# BrainFuino.net
KiCad netlist of a schematic drawn in EAGLE
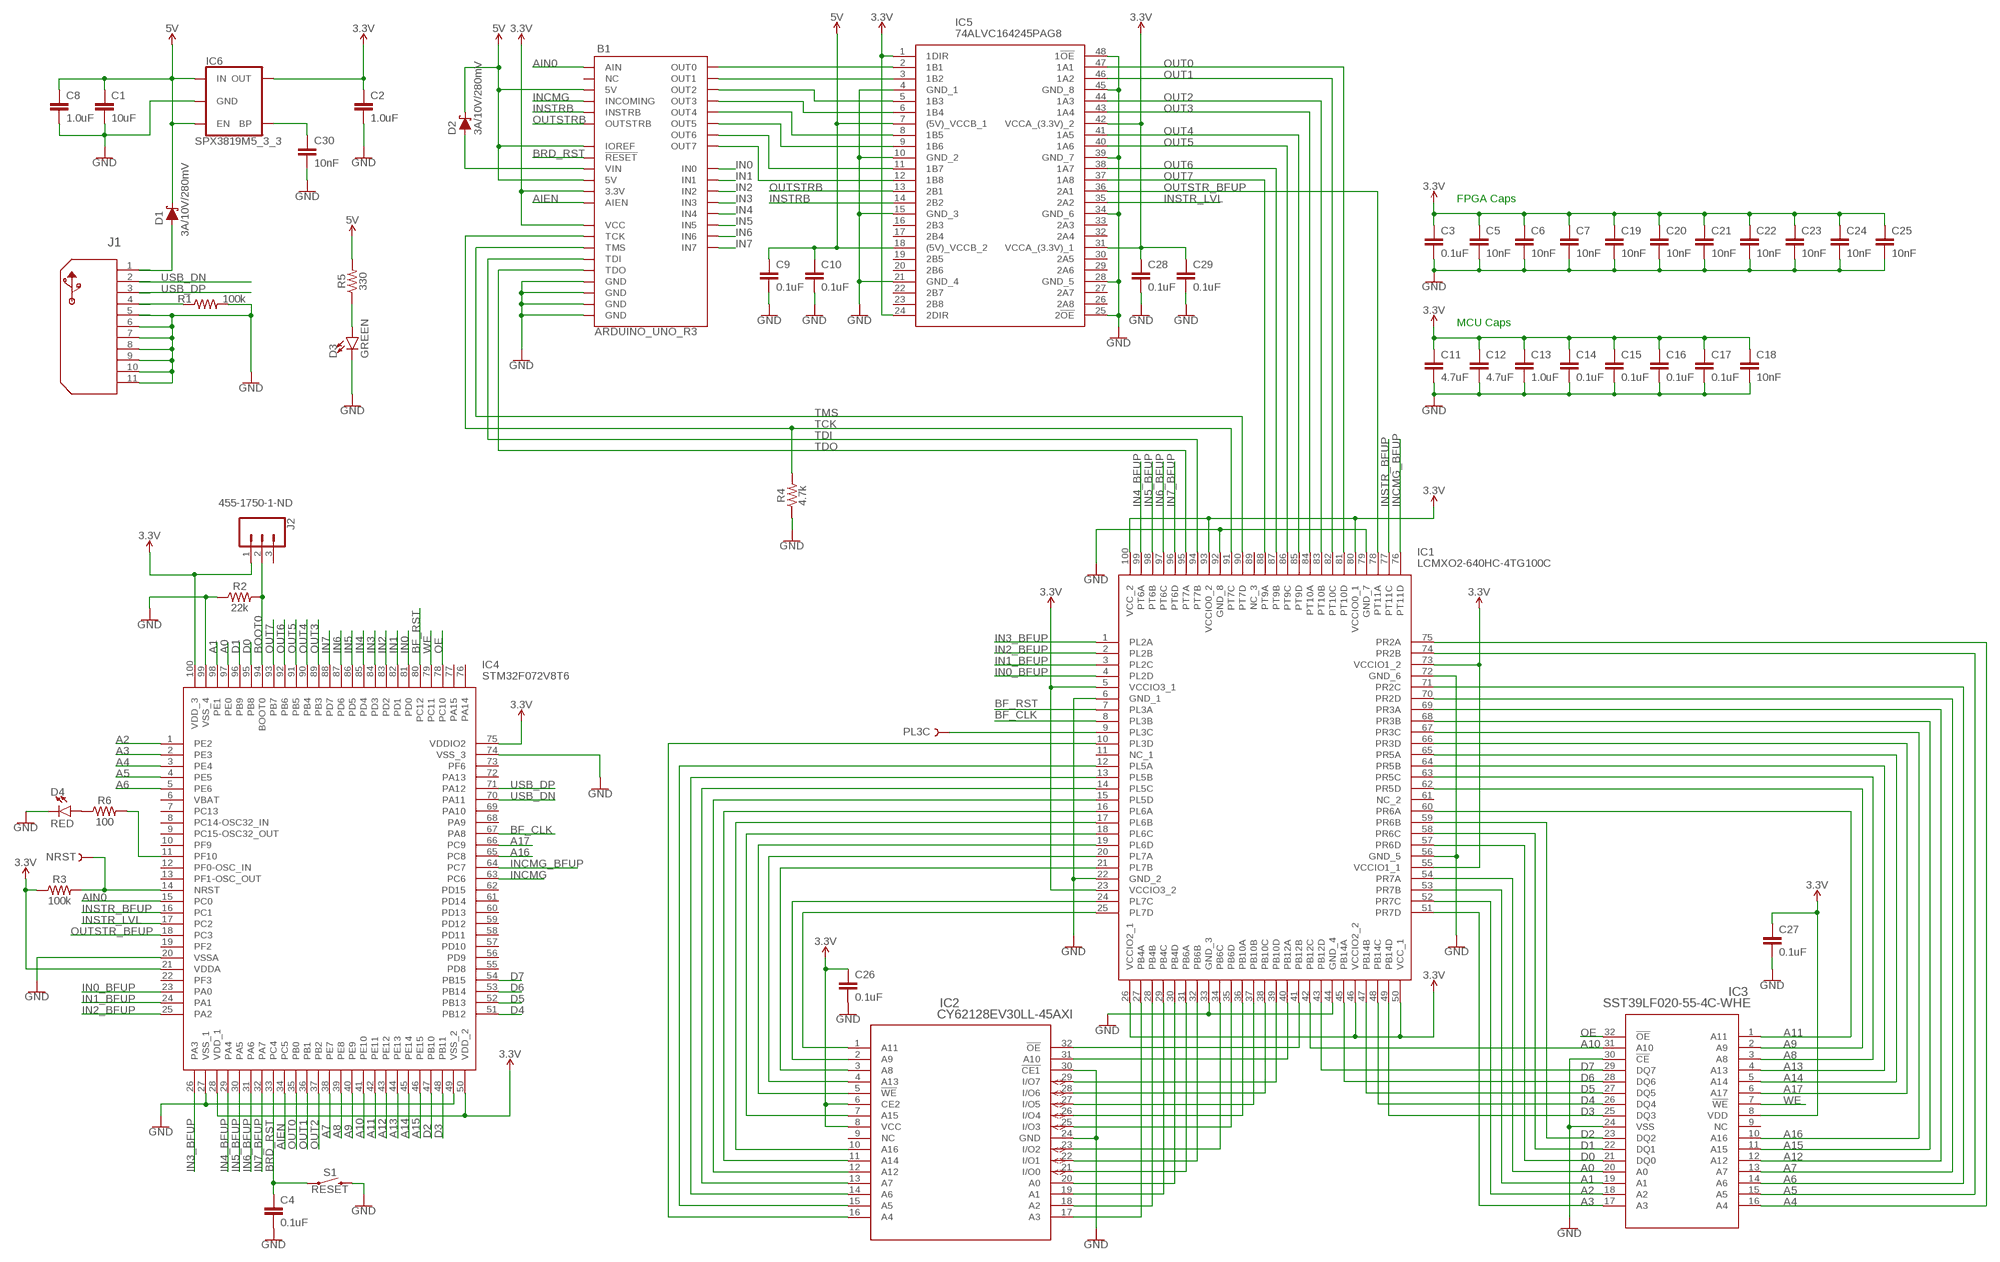
[diagram p0: schematic, sheet 1]

(export (version "E")
  (design (tool "Eeschema 10.0.6"))
  (components
    (comp (ref "B1")
      (value "ARDUINO_UNO_R3")
      (footprint "eagle-import:ARDUINO_R3")
      (libsource (lib "eagle-import") (part "ARDUINO_UNO_R3"))
    )
    (comp (ref "C1")
      (value "10uF")
      (footprint "eagle-import:0603")
      (libsource (lib "eagle-import") (part "10UF-0603-6.3V-20%"))
    )
    (comp (ref "C2")
      (value "1.0uF")
      (footprint "eagle-import:0603")
      (libsource (lib "eagle-import") (part "1.0UF-0603-16V-10%-X7R"))
    )
    (comp (ref "C3")
      (value "0.1uF")
      (footprint "eagle-import:0603")
      (libsource (lib "eagle-import") (part "0.1UF-0603-25V-5%"))
    )
    (comp (ref "C4")
      (value "0.1uF")
      (footprint "eagle-import:0603")
      (libsource (lib "eagle-import") (part "0.1UF-0603-25V-5%"))
    )
    (comp (ref "C5")
      (value "10nF")
      (footprint "eagle-import:0603")
      (libsource (lib "eagle-import") (part "10NF-0603-50V-10%"))
    )
    (comp (ref "C6")
      (value "10nF")
      (footprint "eagle-import:0603")
      (libsource (lib "eagle-import") (part "10NF-0603-50V-10%"))
    )
    (comp (ref "C7")
      (value "10nF")
      (footprint "eagle-import:0603")
      (libsource (lib "eagle-import") (part "10NF-0603-50V-10%"))
    )
    (comp (ref "C8")
      (value "1.0uF")
      (footprint "eagle-import:0603")
      (libsource (lib "eagle-import") (part "1.0UF-0603-16V-10%-X7R"))
    )
    (comp (ref "C9")
      (value "0.1uF")
      (footprint "eagle-import:0603")
      (libsource (lib "eagle-import") (part "0.1UF-0603-25V-5%"))
    )
    (comp (ref "C10")
      (value "0.1uF")
      (footprint "eagle-import:0603")
      (libsource (lib "eagle-import") (part "0.1UF-0603-25V-5%"))
    )
    (comp (ref "C11")
      (value "4.7uF")
      (footprint "eagle-import:0603")
      (libsource (lib "eagle-import") (part "4.7UF-0603-6.3V-(10%)"))
    )
    (comp (ref "C12")
      (value "4.7uF")
      (footprint "eagle-import:0603")
      (libsource (lib "eagle-import") (part "4.7UF-0603-6.3V-(10%)"))
    )
    (comp (ref "C13")
      (value "1.0uF")
      (footprint "eagle-import:0603")
      (libsource (lib "eagle-import") (part "1.0UF-0603-16V-10%"))
    )
    (comp (ref "C14")
      (value "0.1uF")
      (footprint "eagle-import:0603")
      (libsource (lib "eagle-import") (part "0.1UF-0603-25V-5%"))
    )
    (comp (ref "C15")
      (value "0.1uF")
      (footprint "eagle-import:0603")
      (libsource (lib "eagle-import") (part "0.1UF-0603-25V-5%"))
    )
    (comp (ref "C16")
      (value "0.1uF")
      (footprint "eagle-import:0603")
      (libsource (lib "eagle-import") (part "0.1UF-0603-25V-5%"))
    )
    (comp (ref "C17")
      (value "0.1uF")
      (footprint "eagle-import:0603")
      (libsource (lib "eagle-import") (part "0.1UF-0603-25V-5%"))
    )
    (comp (ref "C18")
      (value "10nF")
      (footprint "eagle-import:0603")
      (libsource (lib "eagle-import") (part "10NF-0603-50V-10%"))
    )
    (comp (ref "C19")
      (value "10nF")
      (footprint "eagle-import:0603")
      (libsource (lib "eagle-import") (part "10NF-0603-50V-10%"))
    )
    (comp (ref "C20")
      (value "10nF")
      (footprint "eagle-import:0603")
      (libsource (lib "eagle-import") (part "10NF-0603-50V-10%"))
    )
    (comp (ref "C21")
      (value "10nF")
      (footprint "eagle-import:0603")
      (libsource (lib "eagle-import") (part "10NF-0603-50V-10%"))
    )
    (comp (ref "C22")
      (value "10nF")
      (footprint "eagle-import:0603")
      (libsource (lib "eagle-import") (part "10NF-0603-50V-10%"))
    )
    (comp (ref "C23")
      (value "10nF")
      (footprint "eagle-import:0603")
      (libsource (lib "eagle-import") (part "10NF-0603-50V-10%"))
    )
    (comp (ref "C24")
      (value "10nF")
      (footprint "eagle-import:0603")
      (libsource (lib "eagle-import") (part "10NF-0603-50V-10%"))
    )
    (comp (ref "C25")
      (value "10nF")
      (footprint "eagle-import:0603")
      (libsource (lib "eagle-import") (part "10NF-0603-50V-10%"))
    )
    (comp (ref "C26")
      (value "0.1uF")
      (footprint "eagle-import:0603")
      (libsource (lib "eagle-import") (part "0.1UF-0603-25V-5%"))
    )
    (comp (ref "C27")
      (value "0.1uF")
      (footprint "eagle-import:0603")
      (libsource (lib "eagle-import") (part "0.1UF-0603-25V-5%"))
    )
    (comp (ref "C28")
      (value "0.1uF")
      (footprint "eagle-import:0603")
      (libsource (lib "eagle-import") (part "0.1UF-0603-25V-5%"))
    )
    (comp (ref "C29")
      (value "0.1uF")
      (footprint "eagle-import:0603")
      (libsource (lib "eagle-import") (part "0.1UF-0603-25V-5%"))
    )
    (comp (ref "C30")
      (value "10nF")
      (footprint "eagle-import:0603")
      (libsource (lib "eagle-import") (part "10NF-0603-50V-10%"))
    )
    (comp (ref "D1")
      (value "3A/10V/280mV")
      (footprint "eagle-import:SOD-323")
      (libsource (lib "eagle-import") (part "DIODE-SCHOTTKY-BAT60A"))
    )
    (comp (ref "D2")
      (value "3A/10V/280mV")
      (footprint "eagle-import:SOD-323")
      (libsource (lib "eagle-import") (part "DIODE-SCHOTTKY-BAT60A"))
    )
    (comp (ref "D3")
      (value "GREEN")
      (footprint "eagle-import:LED-0603")
      (libsource (lib "eagle-import") (part "LED-GREEN0603"))
    )
    (comp (ref "D4")
      (value "RED")
      (footprint "eagle-import:LED-0603")
      (libsource (lib "eagle-import") (part "LED-RED0603"))
    )
    (comp (ref "IC1")
      (value "LCMXO2-640HC-4TG100C")
      (footprint "eagle-import:QFP50P1600X1600X160-100N")
      (fields (field (name "MOUSER_PART_NUMBER") "842-XO2640HC4TG100C"))
      (libsource (lib "eagle-import") (part "LCMXO2-640HC-4TG100C"))
    )
    (comp (ref "IC2")
      (value "CY62128EV30LL-45AXI")
      (footprint "eagle-import:TSOP-32")
      (libsource (lib "eagle-import") (part "CY62128EV30LL-45AXI"))
    )
    (comp (ref "IC3")
      (value "SST39LF020-55-4C-WHE")
      (footprint "eagle-import:TSOP32_WH_SST")
      (fields (field (name "COPYRIGHT") "Copyright (C) 2018 Accelerated Designs. All rights reserved"))
      (libsource (lib "eagle-import") (part "SST39LF020-55-4C-WHE"))
    )
    (comp (ref "IC4")
      (value "STM32F072V8T6")
      (footprint "eagle-import:QFP50P1600X1600X160-100N")
      (fields (field (name "MOUSER_PART_NUMBER") "511-STM32F072V8T6"))
      (libsource (lib "eagle-import") (part "STM32F072V8T6"))
    )
    (comp (ref "IC5")
      (value "74ALVC164245PAG8")
      (footprint "eagle-import:SOP50P810X120-48N")
      (fields (field (name "MOUSER_PART_NUMBER") "972-74ALVC164245PAG8"))
      (libsource (lib "eagle-import") (part "74ALVC164245PAG8"))
    )
    (comp (ref "IC6")
      (value "SPX3819M5_3_3")
      (footprint "eagle-import:SOT23-5")
      (libsource (lib "eagle-import") (part "V_REG_SPX3819-SOT23-5"))
    )
    (comp (ref "J1")
      (value "1981568-1")
      (footprint "eagle-import:CONN5_1981568-1_TEC")
      (fields (field (name "COPYRIGHT") "Copyright (C) 2016 Accelerated Designs. All rights reserved"))
      (libsource (lib "eagle-import") (part "1981568-1"))
    )
    (comp (ref "J2")
      (value "455-1750-1-ND")
      (footprint "eagle-import:1X03")
      (libsource (lib "eagle-import") (part "CONN_03"))
    )
    (comp (ref "NRST")
      (value "TEST-POINTPOGO_PTH")
      (footprint "eagle-import:1X01_NO_SILK")
      (libsource (lib "eagle-import") (part "TEST-POINTPOGO_PTH"))
    )
    (comp (ref "PL3C")
      (value "TEST-POINTPOGO_PTH")
      (footprint "eagle-import:1X01_NO_SILK")
      (libsource (lib "eagle-import") (part "TEST-POINTPOGO_PTH"))
    )
    (comp (ref "R1")
      (value "100k")
      (footprint "eagle-import:0603")
      (libsource (lib "eagle-import") (part "100KOHM-0603-1/10W-1%"))
    )
    (comp (ref "R2")
      (value "22k")
      (footprint "eagle-import:0603")
      (libsource (lib "eagle-import") (part "22KOHM-0603-1/10W-1%"))
    )
    (comp (ref "R3")
      (value "100k")
      (footprint "eagle-import:0603")
      (libsource (lib "eagle-import") (part "100KOHM-0603-1/10W-1%"))
    )
    (comp (ref "R4")
      (value "4.7k")
      (footprint "eagle-import:0603")
      (libsource (lib "eagle-import") (part "4.7KOHM-0603-1/10W-1%"))
    )
    (comp (ref "R5")
      (value "330")
      (footprint "eagle-import:0603")
      (libsource (lib "eagle-import") (part "330OHM-0603-1/10W-1%"))
    )
    (comp (ref "R6")
      (value "100")
      (footprint "eagle-import:0603")
      (libsource (lib "eagle-import") (part "100OHM-0603-1/10W-1%"))
    )
    (comp (ref "S1")
      (value "RESET")
      (footprint "eagle-import:TACTILE_SWITCH_SMD_6.2MM_TALL")
      (libsource (lib "eagle-import") (part "MOMENTARY-SWITCH-SPST-SMD-6.2MM-TALL"))
    )
  )
  (nets
    (net (code "1") (name "/A0") (class "Default")
      (node (ref "IC1") (pin "54") (pinfunction "PR7A_54") (pintype "bidirectional"))
      (node (ref "IC3") (pin "20") (pinfunction "A0_20") (pintype "input"))
      (node (ref "IC4") (pin "97") (pinfunction "PE0_97") (pintype "bidirectional"))
    )
    (net (code "2") (name "/A1") (class "Default")
      (node (ref "IC1") (pin "53") (pinfunction "PR7B_53") (pintype "bidirectional"))
      (node (ref "IC3") (pin "19") (pinfunction "A1_19") (pintype "input"))
      (node (ref "IC4") (pin "98") (pinfunction "PE1_98") (pintype "bidirectional"))
    )
    (net (code "3") (name "/A2") (class "Default")
      (node (ref "IC1") (pin "52") (pinfunction "PR7C_52") (pintype "bidirectional"))
      (node (ref "IC3") (pin "18") (pinfunction "A2_18") (pintype "input"))
      (node (ref "IC4") (pin "1") (pinfunction "PE2_1") (pintype "bidirectional"))
    )
    (net (code "4") (name "/A3") (class "Default")
      (node (ref "IC1") (pin "51") (pinfunction "PR7D_51") (pintype "bidirectional"))
      (node (ref "IC3") (pin "17") (pinfunction "A3_17") (pintype "input"))
      (node (ref "IC4") (pin "2") (pinfunction "PE3_2") (pintype "bidirectional"))
    )
    (net (code "5") (name "/A4") (class "Default")
      (node (ref "IC1") (pin "75") (pinfunction "PR2A_75") (pintype "bidirectional"))
      (node (ref "IC3") (pin "16") (pinfunction "A4_16") (pintype "input"))
      (node (ref "IC4") (pin "3") (pinfunction "PE4_3") (pintype "bidirectional"))
    )
    (net (code "6") (name "/A5") (class "Default")
      (node (ref "IC1") (pin "74") (pinfunction "PR2B_74") (pintype "bidirectional"))
      (node (ref "IC3") (pin "15") (pinfunction "A5_15") (pintype "input"))
      (node (ref "IC4") (pin "4") (pinfunction "PE5_4") (pintype "bidirectional"))
    )
    (net (code "7") (name "/A6") (class "Default")
      (node (ref "IC1") (pin "71") (pinfunction "PR2C_71") (pintype "bidirectional"))
      (node (ref "IC3") (pin "14") (pinfunction "A6_14") (pintype "input"))
      (node (ref "IC4") (pin "5") (pinfunction "PE6_5") (pintype "bidirectional"))
    )
    (net (code "8") (name "/A7") (class "Default")
      (node (ref "IC1") (pin "70") (pinfunction "PR2D_70") (pintype "bidirectional"))
      (node (ref "IC3") (pin "13") (pinfunction "A7_13") (pintype "input"))
      (node (ref "IC4") (pin "38") (pinfunction "PE7_38") (pintype "bidirectional"))
    )
    (net (code "9") (name "/A8") (class "Default")
      (node (ref "IC1") (pin "63") (pinfunction "PR5C_63") (pintype "bidirectional"))
      (node (ref "IC3") (pin "3") (pinfunction "A8_3") (pintype "input"))
      (node (ref "IC4") (pin "39") (pinfunction "PE8_39") (pintype "bidirectional"))
    )
    (net (code "10") (name "/A9") (class "Default")
      (node (ref "IC1") (pin "62") (pinfunction "PR5D_62") (pintype "bidirectional"))
      (node (ref "IC3") (pin "2") (pinfunction "A9_2") (pintype "input"))
      (node (ref "IC4") (pin "40") (pinfunction "PE9_40") (pintype "bidirectional"))
    )
    (net (code "11") (name "/A10") (class "Default")
      (node (ref "IC1") (pin "42") (pinfunction "PB12C_42") (pintype "bidirectional"))
      (node (ref "IC3") (pin "31") (pinfunction "A10_31") (pintype "input"))
      (node (ref "IC4") (pin "41") (pinfunction "PE10_41") (pintype "bidirectional"))
    )
    (net (code "12") (name "/A11") (class "Default")
      (node (ref "IC1") (pin "60") (pinfunction "PR6A_60") (pintype "bidirectional"))
      (node (ref "IC3") (pin "1") (pinfunction "A11_1") (pintype "input"))
      (node (ref "IC4") (pin "42") (pinfunction "PE11_42") (pintype "bidirectional"))
    )
    (net (code "13") (name "/A12") (class "Default")
      (node (ref "IC1") (pin "69") (pinfunction "PR3A_69") (pintype "bidirectional"))
      (node (ref "IC3") (pin "12") (pinfunction "A12_12") (pintype "input"))
      (node (ref "IC4") (pin "43") (pinfunction "PE12_43") (pintype "bidirectional"))
    )
    (net (code "14") (name "/A13") (class "Default")
      (node (ref "IC1") (pin "64") (pinfunction "PR5B_64") (pintype "bidirectional"))
      (node (ref "IC3") (pin "4") (pinfunction "A13_4") (pintype "input"))
      (node (ref "IC4") (pin "44") (pinfunction "PE13_44") (pintype "bidirectional"))
    )
    (net (code "15") (name "/A14") (class "Default")
      (node (ref "IC1") (pin "65") (pinfunction "PR5A_65") (pintype "bidirectional"))
      (node (ref "IC3") (pin "5") (pinfunction "A14_5") (pintype "input"))
      (node (ref "IC4") (pin "45") (pinfunction "PE14_45") (pintype "bidirectional"))
    )
    (net (code "16") (name "/A15") (class "Default")
      (node (ref "IC1") (pin "68") (pinfunction "PR3B_68") (pintype "bidirectional"))
      (node (ref "IC3") (pin "11") (pinfunction "A15_11") (pintype "input"))
      (node (ref "IC4") (pin "46") (pinfunction "PE15_46") (pintype "bidirectional"))
    )
    (net (code "17") (name "/A16") (class "Default")
      (node (ref "IC1") (pin "67") (pinfunction "PR3C_67") (pintype "bidirectional"))
      (node (ref "IC3") (pin "10") (pinfunction "A16_10") (pintype "input"))
      (node (ref "IC4") (pin "65") (pinfunction "PC8_65") (pintype "bidirectional"))
    )
    (net (code "18") (name "/A17") (class "Default")
      (node (ref "IC1") (pin "66") (pinfunction "PR3D_66") (pintype "bidirectional"))
      (node (ref "IC3") (pin "6") (pinfunction "A17_6") (pintype "input"))
      (node (ref "IC4") (pin "66") (pinfunction "PC9_66") (pintype "bidirectional"))
    )
    (net (code "19") (name "/AIEN") (class "Default")
      (node (ref "B1") (pin "AREF") (pinfunction "AIEN_AREF") (pintype "bidirectional"))
      (node (ref "IC4") (pin "34") (pinfunction "PC5_34") (pintype "bidirectional"))
    )
    (net (code "20") (name "/AIN0") (class "Default")
      (node (ref "B1") (pin "AIN") (pinfunction "AIN_AIN") (pintype "bidirectional"))
      (node (ref "IC4") (pin "15") (pinfunction "PC0_15") (pintype "bidirectional"))
    )
    (net (code "21") (name "/BF_CLK") (class "Default")
      (node (ref "IC1") (pin "8") (pinfunction "PL3B_8") (pintype "bidirectional"))
      (node (ref "IC4") (pin "67") (pinfunction "PA8_67") (pintype "bidirectional"))
    )
    (net (code "22") (name "/BF_RST") (class "Default")
      (node (ref "IC1") (pin "7") (pinfunction "PL3A_7") (pintype "bidirectional"))
      (node (ref "IC4") (pin "80") (pinfunction "PC12_80") (pintype "bidirectional"))
    )
    (net (code "23") (name "/BOOT0") (class "Default")
      (node (ref "IC4") (pin "94") (pinfunction "BOOT0_94") (pintype "bidirectional"))
      (node (ref "J2") (pin "2") (pinfunction "2_2") (pintype "passive"))
      (node (ref "R2") (pin "2") (pinfunction "2_2") (pintype "passive"))
    )
    (net (code "24") (name "/BRD_RST") (class "Default")
      (node (ref "B1") (pin "RESET@1") (pinfunction "~{RESET}_RESET@1") (pintype "bidirectional"))
      (node (ref "C4") (pin "1") (pinfunction "1_1") (pintype "passive"))
      (node (ref "IC4") (pin "33") (pinfunction "PC4_33") (pintype "bidirectional"))
      (node (ref "S1") (pin "A2") (pinfunction "1_A2") (pintype "passive"))
    )
    (net (code "25") (name "/D0") (class "Default")
      (node (ref "IC1") (pin "57") (pinfunction "PR6D_57") (pintype "bidirectional"))
      (node (ref "IC3") (pin "21") (pinfunction "DQ0_21") (pintype "bidirectional"))
      (node (ref "IC4") (pin "95") (pinfunction "PB8_95") (pintype "bidirectional"))
    )
    (net (code "26") (name "/D1") (class "Default")
      (node (ref "IC1") (pin "58") (pinfunction "PR6C_58") (pintype "bidirectional"))
      (node (ref "IC3") (pin "22") (pinfunction "DQ1_22") (pintype "bidirectional"))
      (node (ref "IC4") (pin "96") (pinfunction "PB9_96") (pintype "bidirectional"))
    )
    (net (code "27") (name "/D2") (class "Default")
      (node (ref "IC1") (pin "59") (pinfunction "PR6B_59") (pintype "bidirectional"))
      (node (ref "IC3") (pin "23") (pinfunction "DQ2_23") (pintype "bidirectional"))
      (node (ref "IC4") (pin "47") (pinfunction "PB10_47") (pintype "bidirectional"))
    )
    (net (code "28") (name "/D3") (class "Default")
      (node (ref "IC1") (pin "49") (pinfunction "PB14D_49") (pintype "bidirectional"))
      (node (ref "IC3") (pin "25") (pinfunction "DQ3_25") (pintype "bidirectional"))
      (node (ref "IC4") (pin "48") (pinfunction "PB11_48") (pintype "bidirectional"))
    )
    (net (code "29") (name "/D4") (class "Default")
      (node (ref "IC1") (pin "48") (pinfunction "PB14C_48") (pintype "bidirectional"))
      (node (ref "IC3") (pin "26") (pinfunction "DQ4_26") (pintype "bidirectional"))
      (node (ref "IC4") (pin "51") (pinfunction "PB12_51") (pintype "bidirectional"))
    )
    (net (code "30") (name "/D5") (class "Default")
      (node (ref "IC1") (pin "47") (pinfunction "PB14B_47") (pintype "bidirectional"))
      (node (ref "IC3") (pin "27") (pinfunction "DQ5_27") (pintype "bidirectional"))
      (node (ref "IC4") (pin "52") (pinfunction "PB13_52") (pintype "bidirectional"))
    )
    (net (code "31") (name "/D6") (class "Default")
      (node (ref "IC1") (pin "45") (pinfunction "PB14A_45") (pintype "bidirectional"))
      (node (ref "IC3") (pin "28") (pinfunction "DQ6_28") (pintype "bidirectional"))
      (node (ref "IC4") (pin "53") (pinfunction "PB14_53") (pintype "bidirectional"))
    )
    (net (code "32") (name "/D7") (class "Default")
      (node (ref "IC1") (pin "43") (pinfunction "PB12D_43") (pintype "bidirectional"))
      (node (ref "IC3") (pin "29") (pinfunction "DQ7_29") (pintype "bidirectional"))
      (node (ref "IC4") (pin "54") (pinfunction "PB15_54") (pintype "bidirectional"))
    )
    (net (code "33") (name "/IN0") (class "Default")
      (node (ref "B1") (pin "IN0") (pinfunction "IN0_IN0") (pintype "bidirectional"))
      (node (ref "IC4") (pin "81") (pinfunction "PD0_81") (pintype "bidirectional"))
    )
    (net (code "34") (name "/IN0_BFUP") (class "Default")
      (node (ref "IC1") (pin "4") (pinfunction "PL2D_4") (pintype "bidirectional"))
      (node (ref "IC4") (pin "23") (pinfunction "PA0_23") (pintype "bidirectional"))
    )
    (net (code "35") (name "/IN1") (class "Default")
      (node (ref "B1") (pin "IN1") (pinfunction "IN1_IN1") (pintype "bidirectional"))
      (node (ref "IC4") (pin "82") (pinfunction "PD1_82") (pintype "bidirectional"))
    )
    (net (code "36") (name "/IN1_BFUP") (class "Default")
      (node (ref "IC1") (pin "3") (pinfunction "PL2C_3") (pintype "bidirectional"))
      (node (ref "IC4") (pin "24") (pinfunction "PA1_24") (pintype "bidirectional"))
    )
    (net (code "37") (name "/IN2") (class "Default")
      (node (ref "B1") (pin "IN2") (pinfunction "IN2_IN2") (pintype "bidirectional"))
      (node (ref "IC4") (pin "83") (pinfunction "PD2_83") (pintype "bidirectional"))
    )
    (net (code "38") (name "/IN2_BFUP") (class "Default")
      (node (ref "IC1") (pin "2") (pinfunction "PL2B_2") (pintype "bidirectional"))
      (node (ref "IC4") (pin "25") (pinfunction "PA2_25") (pintype "bidirectional"))
    )
    (net (code "39") (name "/IN3") (class "Default")
      (node (ref "B1") (pin "IN3") (pinfunction "IN3_IN3") (pintype "bidirectional"))
      (node (ref "IC4") (pin "84") (pinfunction "PD3_84") (pintype "bidirectional"))
    )
    (net (code "40") (name "/IN3_BFUP") (class "Default")
      (node (ref "IC1") (pin "1") (pinfunction "PL2A_1") (pintype "bidirectional"))
      (node (ref "IC4") (pin "26") (pinfunction "PA3_26") (pintype "bidirectional"))
    )
    (net (code "41") (name "/IN4") (class "Default")
      (node (ref "B1") (pin "IN4") (pinfunction "IN4_IN4") (pintype "bidirectional"))
      (node (ref "IC4") (pin "85") (pinfunction "PD4_85") (pintype "bidirectional"))
    )
    (net (code "42") (name "/IN4_BFUP") (class "Default")
      (node (ref "IC1") (pin "99") (pinfunction "PT6A_99") (pintype "bidirectional"))
      (node (ref "IC4") (pin "29") (pinfunction "PA4_29") (pintype "bidirectional"))
    )
    (net (code "43") (name "/IN5") (class "Default")
      (node (ref "B1") (pin "IN5") (pinfunction "IN5_IN5") (pintype "bidirectional"))
      (node (ref "IC4") (pin "86") (pinfunction "PD5_86") (pintype "bidirectional"))
    )
    (net (code "44") (name "/IN5_BFUP") (class "Default")
      (node (ref "IC1") (pin "98") (pinfunction "PT6B_98") (pintype "bidirectional"))
      (node (ref "IC4") (pin "30") (pinfunction "PA5_30") (pintype "bidirectional"))
    )
    (net (code "45") (name "/IN6") (class "Default")
      (node (ref "B1") (pin "IN6") (pinfunction "IN6_IN6") (pintype "bidirectional"))
      (node (ref "IC4") (pin "87") (pinfunction "PD6_87") (pintype "bidirectional"))
    )
    (net (code "46") (name "/IN6_BFUP") (class "Default")
      (node (ref "IC1") (pin "97") (pinfunction "PT6C_97") (pintype "bidirectional"))
      (node (ref "IC4") (pin "31") (pinfunction "PA6_31") (pintype "bidirectional"))
    )
    (net (code "47") (name "/IN7") (class "Default")
      (node (ref "B1") (pin "IN7") (pinfunction "IN7_IN7") (pintype "bidirectional"))
      (node (ref "IC4") (pin "88") (pinfunction "PD7_88") (pintype "bidirectional"))
    )
    (net (code "48") (name "/IN7_BFUP") (class "Default")
      (node (ref "IC1") (pin "96") (pinfunction "PT6D_96") (pintype "bidirectional"))
      (node (ref "IC4") (pin "32") (pinfunction "PA7_32") (pintype "bidirectional"))
    )
    (net (code "49") (name "/INCMG") (class "Default")
      (node (ref "B1") (pin "INCOMING") (pinfunction "INCOMING_INCOMING") (pintype "bidirectional"))
      (node (ref "IC4") (pin "63") (pinfunction "PC6_63") (pintype "bidirectional"))
    )
    (net (code "50") (name "/INCMG_BFUP") (class "Default")
      (node (ref "IC1") (pin "76") (pinfunction "PT11D_76") (pintype "bidirectional"))
      (node (ref "IC4") (pin "64") (pinfunction "PC7_64") (pintype "bidirectional"))
    )
    (net (code "51") (name "/INSTRB") (class "Default")
      (node (ref "B1") (pin "INST") (pinfunction "INSTRB_INST") (pintype "bidirectional"))
      (node (ref "IC5") (pin "14") (pinfunction "2B2_14") (pintype "bidirectional"))
    )
    (net (code "52") (name "/INSTR_BFUP") (class "Default")
      (node (ref "IC1") (pin "77") (pinfunction "PT11C_77") (pintype "bidirectional"))
      (node (ref "IC4") (pin "16") (pinfunction "PC1_16") (pintype "bidirectional"))
    )
    (net (code "53") (name "/INSTR_LVL") (class "Default")
      (node (ref "IC4") (pin "17") (pinfunction "PC2_17") (pintype "bidirectional"))
      (node (ref "IC5") (pin "35") (pinfunction "2A2_35") (pintype "bidirectional"))
    )
    (net (code "54") (name "/OE") (class "Default")
      (node (ref "IC3") (pin "32") (pinfunction "~{OE}_32") (pintype "output"))
      (node (ref "IC4") (pin "78") (pinfunction "PC10_78") (pintype "bidirectional"))
    )
    (net (code "55") (name "/OUT0") (class "Default")
      (node (ref "IC1") (pin "81") (pinfunction "PT10D_81") (pintype "bidirectional"))
      (node (ref "IC4") (pin "35") (pinfunction "PB0_35") (pintype "bidirectional"))
      (node (ref "IC5") (pin "47") (pinfunction "1A1_47") (pintype "bidirectional"))
    )
    (net (code "56") (name "/OUT1") (class "Default")
      (node (ref "IC1") (pin "82") (pinfunction "PT10C_82") (pintype "bidirectional"))
      (node (ref "IC4") (pin "36") (pinfunction "PB1_36") (pintype "bidirectional"))
      (node (ref "IC5") (pin "46") (pinfunction "1A2_46") (pintype "bidirectional"))
    )
    (net (code "57") (name "/OUT2") (class "Default")
      (node (ref "IC1") (pin "83") (pinfunction "PT10B_83") (pintype "bidirectional"))
      (node (ref "IC4") (pin "37") (pinfunction "PB2_37") (pintype "bidirectional"))
      (node (ref "IC5") (pin "44") (pinfunction "1A3_44") (pintype "bidirectional"))
    )
    (net (code "58") (name "/OUT3") (class "Default")
      (node (ref "IC1") (pin "84") (pinfunction "PT10A_84") (pintype "bidirectional"))
      (node (ref "IC4") (pin "89") (pinfunction "PB3_89") (pintype "bidirectional"))
      (node (ref "IC5") (pin "43") (pinfunction "1A4_43") (pintype "bidirectional"))
    )
    (net (code "59") (name "/OUT4") (class "Default")
      (node (ref "IC1") (pin "85") (pinfunction "PT9D_85") (pintype "bidirectional"))
      (node (ref "IC4") (pin "90") (pinfunction "PB4_90") (pintype "bidirectional"))
      (node (ref "IC5") (pin "41") (pinfunction "1A5_41") (pintype "bidirectional"))
    )
    (net (code "60") (name "/OUT5") (class "Default")
      (node (ref "IC1") (pin "86") (pinfunction "PT9C_86") (pintype "bidirectional"))
      (node (ref "IC4") (pin "91") (pinfunction "PB5_91") (pintype "bidirectional"))
      (node (ref "IC5") (pin "40") (pinfunction "1A6_40") (pintype "bidirectional"))
    )
    (net (code "61") (name "/OUT6") (class "Default")
      (node (ref "IC1") (pin "87") (pinfunction "PT9B_87") (pintype "bidirectional"))
      (node (ref "IC4") (pin "92") (pinfunction "PB6_92") (pintype "bidirectional"))
      (node (ref "IC5") (pin "38") (pinfunction "1A7_38") (pintype "bidirectional"))
    )
    (net (code "62") (name "/OUT7") (class "Default")
      (node (ref "IC1") (pin "88") (pinfunction "PT9A_88") (pintype "bidirectional"))
      (node (ref "IC4") (pin "93") (pinfunction "PB7_93") (pintype "bidirectional"))
      (node (ref "IC5") (pin "37") (pinfunction "1A8_37") (pintype "bidirectional"))
    )
    (net (code "63") (name "/OUTSTRB") (class "Default")
      (node (ref "B1") (pin "OUTST") (pinfunction "OUTSTRB_OUTST") (pintype "bidirectional"))
      (node (ref "IC5") (pin "13") (pinfunction "2B1_13") (pintype "bidirectional"))
    )
    (net (code "64") (name "/OUTSTR_BFUP") (class "Default")
      (node (ref "IC1") (pin "78") (pinfunction "PT11A_78") (pintype "bidirectional"))
      (node (ref "IC4") (pin "18") (pinfunction "PC3_18") (pintype "bidirectional"))
      (node (ref "IC5") (pin "36") (pinfunction "2A1_36") (pintype "bidirectional"))
    )
    (net (code "65") (name "/TCK") (class "Default")
      (node (ref "B1") (pin "TCK") (pinfunction "TCK_TCK") (pintype "bidirectional"))
      (node (ref "IC1") (pin "91") (pinfunction "PT7C_91") (pintype "bidirectional"))
      (node (ref "R4") (pin "2") (pinfunction "2_2") (pintype "passive"))
    )
    (net (code "66") (name "/TDI") (class "Default")
      (node (ref "B1") (pin "TDI") (pinfunction "TDI_TDI") (pintype "bidirectional"))
      (node (ref "IC1") (pin "94") (pinfunction "PT7B_94") (pintype "bidirectional"))
    )
    (net (code "67") (name "/TDO") (class "Default")
      (node (ref "B1") (pin "TDO") (pinfunction "TDO_TDO") (pintype "bidirectional"))
      (node (ref "IC1") (pin "95") (pinfunction "PT7A_95") (pintype "bidirectional"))
    )
    (net (code "68") (name "/TMS") (class "Default")
      (node (ref "B1") (pin "TMS") (pinfunction "TMS_TMS") (pintype "bidirectional"))
      (node (ref "IC1") (pin "90") (pinfunction "PT7D_90") (pintype "bidirectional"))
    )
    (net (code "69") (name "/USB_DN") (class "Default")
      (node (ref "IC4") (pin "70") (pinfunction "PA11_70") (pintype "bidirectional"))
      (node (ref "J1") (pin "2") (pinfunction "2_2") (pintype "passive"))
    )
    (net (code "70") (name "/USB_DP") (class "Default")
      (node (ref "IC4") (pin "71") (pinfunction "PA12_71") (pintype "bidirectional"))
      (node (ref "J1") (pin "3") (pinfunction "3_3") (pintype "passive"))
    )
    (net (code "71") (name "/WE") (class "Default")
      (node (ref "IC3") (pin "7") (pinfunction "~{WE}_7") (pintype "passive"))
      (node (ref "IC4") (pin "79") (pinfunction "PC11_79") (pintype "bidirectional"))
    )
    (net (code "72") (name "3.3V") (class "Default")
      (node (ref "B1") (pin "3.3V") (pinfunction "3.3V_3.3V") (pintype "bidirectional"))
      (node (ref "B1") (pin "VCC") (pinfunction "VCC_VCC") (pintype "bidirectional"))
      (node (ref "C11") (pin "1") (pinfunction "1_1") (pintype "passive"))
      (node (ref "C12") (pin "1") (pinfunction "1_1") (pintype "passive"))
      (node (ref "C13") (pin "1") (pinfunction "1_1") (pintype "passive"))
      (node (ref "C14") (pin "1") (pinfunction "1_1") (pintype "passive"))
      (node (ref "C15") (pin "1") (pinfunction "1_1") (pintype "passive"))
      (node (ref "C16") (pin "1") (pinfunction "1_1") (pintype "passive"))
      (node (ref "C17") (pin "1") (pinfunction "1_1") (pintype "passive"))
      (node (ref "C18") (pin "1") (pinfunction "1_1") (pintype "passive"))
      (node (ref "C19") (pin "1") (pinfunction "1_1") (pintype "passive"))
      (node (ref "C2") (pin "1") (pinfunction "1_1") (pintype "passive"))
      (node (ref "C20") (pin "1") (pinfunction "1_1") (pintype "passive"))
      (node (ref "C21") (pin "1") (pinfunction "1_1") (pintype "passive"))
      (node (ref "C22") (pin "1") (pinfunction "1_1") (pintype "passive"))
      (node (ref "C23") (pin "1") (pinfunction "1_1") (pintype "passive"))
      (node (ref "C24") (pin "1") (pinfunction "1_1") (pintype "passive"))
      (node (ref "C25") (pin "1") (pinfunction "1_1") (pintype "passive"))
      (node (ref "C26") (pin "1") (pinfunction "1_1") (pintype "passive"))
      (node (ref "C27") (pin "1") (pinfunction "1_1") (pintype "passive"))
      (node (ref "C28") (pin "1") (pinfunction "1_1") (pintype "passive"))
      (node (ref "C29") (pin "1") (pinfunction "1_1") (pintype "passive"))
      (node (ref "C3") (pin "1") (pinfunction "1_1") (pintype "passive"))
      (node (ref "C5") (pin "1") (pinfunction "1_1") (pintype "passive"))
      (node (ref "C6") (pin "1") (pinfunction "1_1") (pintype "passive"))
      (node (ref "C7") (pin "1") (pinfunction "1_1") (pintype "passive"))
      (node (ref "IC1") (pin "100") (pinfunction "VCC_2_100") (pintype "bidirectional"))
      (node (ref "IC1") (pin "23") (pinfunction "VCCIO3_2_23") (pintype "bidirectional"))
      (node (ref "IC1") (pin "26") (pinfunction "VCCIO2_1_26") (pintype "bidirectional"))
      (node (ref "IC1") (pin "46") (pinfunction "VCCIO2_2_46") (pintype "bidirectional"))
      (node (ref "IC1") (pin "5") (pinfunction "VCCIO3_1_5") (pintype "bidirectional"))
      (node (ref "IC1") (pin "50") (pinfunction "VCC_1_50") (pintype "bidirectional"))
      (node (ref "IC1") (pin "55") (pinfunction "VCCIO1_1_55") (pintype "bidirectional"))
      (node (ref "IC1") (pin "73") (pinfunction "VCCIO1_2_73") (pintype "bidirectional"))
      (node (ref "IC1") (pin "80") (pinfunction "VCCIO0_1_80") (pintype "bidirectional"))
      (node (ref "IC1") (pin "93") (pinfunction "VCCIO0_2_93") (pintype "bidirectional"))
      (node (ref "IC2") (pin "6") (pinfunction "CE2_6") (pintype "passive"))
      (node (ref "IC2") (pin "8") (pinfunction "VCC_8") (pintype "power_in"))
      (node (ref "IC3") (pin "8") (pinfunction "VDD_8") (pintype "power_in"))
      (node (ref "IC4") (pin "100") (pinfunction "VDD_3_100") (pintype "bidirectional"))
      (node (ref "IC4") (pin "21") (pinfunction "VDDA_21") (pintype "bidirectional"))
      (node (ref "IC4") (pin "28") (pinfunction "VDD_1_28") (pintype "bidirectional"))
      (node (ref "IC4") (pin "50") (pinfunction "VDD_2_50") (pintype "bidirectional"))
      (node (ref "IC4") (pin "75") (pinfunction "VDDIO2_75") (pintype "bidirectional"))
      (node (ref "IC5") (pin "1") (pinfunction "1DIR_1") (pintype "bidirectional"))
      (node (ref "IC5") (pin "24") (pinfunction "2DIR_24") (pintype "bidirectional"))
      (node (ref "IC5") (pin "31") (pinfunction "VCCA_(3.3V)_1_31") (pintype "bidirectional"))
      (node (ref "IC5") (pin "42") (pinfunction "VCCA_(3.3V)_2_42") (pintype "bidirectional"))
      (node (ref "IC6") (pin "5") (pinfunction "OUT_5") (pintype "passive"))
      (node (ref "J2") (pin "1") (pinfunction "1_1") (pintype "passive"))
      (node (ref "R3") (pin "1") (pinfunction "1_1") (pintype "passive"))
    )
    (net (code "73") (name "5V") (class "Default")
      (node (ref "B1") (pin "5V") (pinfunction "5V_5V") (pintype "bidirectional"))
      (node (ref "B1") (pin "5V@1") (pinfunction "5V_5V@1") (pintype "bidirectional"))
      (node (ref "B1") (pin "IOREF") (pinfunction "IOREF_IOREF") (pintype "bidirectional"))
      (node (ref "C1") (pin "1") (pinfunction "1_1") (pintype "passive"))
      (node (ref "C10") (pin "1") (pinfunction "1_1") (pintype "passive"))
      (node (ref "C8") (pin "1") (pinfunction "1_1") (pintype "passive"))
      (node (ref "C9") (pin "1") (pinfunction "1_1") (pintype "passive"))
      (node (ref "D1") (pin "C") (pinfunction "C_C") (pintype "passive"))
      (node (ref "D2") (pin "C") (pinfunction "C_C") (pintype "passive"))
      (node (ref "IC5") (pin "18") (pinfunction "(5V)_VCCB_2_18") (pintype "bidirectional"))
      (node (ref "IC5") (pin "7") (pinfunction "(5V)_VCCB_1_7") (pintype "bidirectional"))
      (node (ref "IC6") (pin "1") (pinfunction "IN_1") (pintype "input"))
      (node (ref "IC6") (pin "3") (pinfunction "EN_3") (pintype "input"))
      (node (ref "R5") (pin "2") (pinfunction "2_2") (pintype "passive"))
    )
    (net (code "74") (name "GND") (class "Default")
      (node (ref "B1") (pin "GND@1") (pinfunction "GND_GND@1") (pintype "bidirectional"))
      (node (ref "B1") (pin "GND@2") (pinfunction "GND_GND@2") (pintype "bidirectional"))
      (node (ref "B1") (pin "GND@3") (pinfunction "GND_GND@3") (pintype "bidirectional"))
      (node (ref "B1") (pin "GND@4") (pinfunction "GND_GND@4") (pintype "bidirectional"))
      (node (ref "C1") (pin "2") (pinfunction "2_2") (pintype "passive"))
      (node (ref "C10") (pin "2") (pinfunction "2_2") (pintype "passive"))
      (node (ref "C11") (pin "2") (pinfunction "2_2") (pintype "passive"))
      (node (ref "C12") (pin "2") (pinfunction "2_2") (pintype "passive"))
      (node (ref "C13") (pin "2") (pinfunction "2_2") (pintype "passive"))
      (node (ref "C14") (pin "2") (pinfunction "2_2") (pintype "passive"))
      (node (ref "C15") (pin "2") (pinfunction "2_2") (pintype "passive"))
      (node (ref "C16") (pin "2") (pinfunction "2_2") (pintype "passive"))
      (node (ref "C17") (pin "2") (pinfunction "2_2") (pintype "passive"))
      (node (ref "C18") (pin "2") (pinfunction "2_2") (pintype "passive"))
      (node (ref "C19") (pin "2") (pinfunction "2_2") (pintype "passive"))
      (node (ref "C2") (pin "2") (pinfunction "2_2") (pintype "passive"))
      (node (ref "C20") (pin "2") (pinfunction "2_2") (pintype "passive"))
      (node (ref "C21") (pin "2") (pinfunction "2_2") (pintype "passive"))
      (node (ref "C22") (pin "2") (pinfunction "2_2") (pintype "passive"))
      (node (ref "C23") (pin "2") (pinfunction "2_2") (pintype "passive"))
      (node (ref "C24") (pin "2") (pinfunction "2_2") (pintype "passive"))
      (node (ref "C25") (pin "2") (pinfunction "2_2") (pintype "passive"))
      (node (ref "C26") (pin "2") (pinfunction "2_2") (pintype "passive"))
      (node (ref "C27") (pin "2") (pinfunction "2_2") (pintype "passive"))
      (node (ref "C28") (pin "2") (pinfunction "2_2") (pintype "passive"))
      (node (ref "C29") (pin "2") (pinfunction "2_2") (pintype "passive"))
      (node (ref "C3") (pin "2") (pinfunction "2_2") (pintype "passive"))
      (node (ref "C30") (pin "2") (pinfunction "2_2") (pintype "passive"))
      (node (ref "C4") (pin "2") (pinfunction "2_2") (pintype "passive"))
      (node (ref "C5") (pin "2") (pinfunction "2_2") (pintype "passive"))
      (node (ref "C6") (pin "2") (pinfunction "2_2") (pintype "passive"))
      (node (ref "C7") (pin "2") (pinfunction "2_2") (pintype "passive"))
      (node (ref "C8") (pin "2") (pinfunction "2_2") (pintype "passive"))
      (node (ref "C9") (pin "2") (pinfunction "2_2") (pintype "passive"))
      (node (ref "D3") (pin "C") (pinfunction "C_C") (pintype "passive"))
      (node (ref "D4") (pin "C") (pinfunction "C_C") (pintype "passive"))
      (node (ref "IC1") (pin "22") (pinfunction "GND_2_22") (pintype "bidirectional"))
      (node (ref "IC1") (pin "33") (pinfunction "GND_3_33") (pintype "bidirectional"))
      (node (ref "IC1") (pin "44") (pinfunction "GND_4_44") (pintype "bidirectional"))
      (node (ref "IC1") (pin "56") (pinfunction "GND_5_56") (pintype "bidirectional"))
      (node (ref "IC1") (pin "6") (pinfunction "GND_1_6") (pintype "bidirectional"))
      (node (ref "IC1") (pin "72") (pinfunction "GND_6_72") (pintype "bidirectional"))
      (node (ref "IC1") (pin "79") (pinfunction "GND_7_79") (pintype "bidirectional"))
      (node (ref "IC1") (pin "92") (pinfunction "GND_8_92") (pintype "bidirectional"))
      (node (ref "IC2") (pin "24") (pinfunction "GND_24") (pintype "power_in"))
      (node (ref "IC2") (pin "30") (pinfunction "~{CE1}_30") (pintype "passive"))
      (node (ref "IC3") (pin "24") (pinfunction "VSS_24") (pintype "power_in"))
      (node (ref "IC3") (pin "30") (pinfunction "~{CE}_30") (pintype "passive"))
      (node (ref "IC4") (pin "20") (pinfunction "VSSA_20") (pintype "bidirectional"))
      (node (ref "IC4") (pin "27") (pinfunction "VSS_1_27") (pintype "bidirectional"))
      (node (ref "IC4") (pin "49") (pinfunction "VSS_2_49") (pintype "bidirectional"))
      (node (ref "IC4") (pin "74") (pinfunction "VSS_3_74") (pintype "bidirectional"))
      (node (ref "IC4") (pin "99") (pinfunction "VSS_4_99") (pintype "bidirectional"))
      (node (ref "IC5") (pin "10") (pinfunction "GND_2_10") (pintype "bidirectional"))
      (node (ref "IC5") (pin "15") (pinfunction "GND_3_15") (pintype "bidirectional"))
      (node (ref "IC5") (pin "21") (pinfunction "GND_4_21") (pintype "bidirectional"))
      (node (ref "IC5") (pin "25") (pinfunction "2~{OE}_25") (pintype "bidirectional"))
      (node (ref "IC5") (pin "28") (pinfunction "GND_5_28") (pintype "bidirectional"))
      (node (ref "IC5") (pin "34") (pinfunction "GND_6_34") (pintype "bidirectional"))
      (node (ref "IC5") (pin "39") (pinfunction "GND_7_39") (pintype "bidirectional"))
      (node (ref "IC5") (pin "4") (pinfunction "GND_1_4") (pintype "bidirectional"))
      (node (ref "IC5") (pin "45") (pinfunction "GND_8_45") (pintype "bidirectional"))
      (node (ref "IC5") (pin "48") (pinfunction "1~{OE}_48") (pintype "bidirectional"))
      (node (ref "IC6") (pin "2") (pinfunction "GND_2") (pintype "input"))
      (node (ref "J1") (pin "10") (pinfunction "10_10") (pintype "passive"))
      (node (ref "J1") (pin "11") (pinfunction "11_11") (pintype "passive"))
      (node (ref "J1") (pin "5") (pinfunction "5_5") (pintype "passive"))
      (node (ref "J1") (pin "6") (pinfunction "6_6") (pintype "passive"))
      (node (ref "J1") (pin "7") (pinfunction "7_7") (pintype "passive"))
      (node (ref "J1") (pin "8") (pinfunction "8_8") (pintype "passive"))
      (node (ref "J1") (pin "9") (pinfunction "9_9") (pintype "passive"))
      (node (ref "R1") (pin "2") (pinfunction "2_2") (pintype "passive"))
      (node (ref "R2") (pin "1") (pinfunction "1_1") (pintype "passive"))
      (node (ref "R4") (pin "1") (pinfunction "1_1") (pintype "passive"))
      (node (ref "S1") (pin "B2") (pinfunction "2_B2") (pintype "passive"))
    )
    (net (code "75") (name "Net-(B1-PadVIN)") (class "Default")
      (node (ref "B1") (pin "VIN") (pinfunction "VIN_VIN") (pintype "bidirectional"))
      (node (ref "D2") (pin "A") (pinfunction "A_A") (pintype "passive"))
    )
    (net (code "76") (name "Net-(D1-PadA)") (class "Default")
      (node (ref "D1") (pin "A") (pinfunction "A_A") (pintype "passive"))
      (node (ref "J1") (pin "1") (pinfunction "1_1") (pintype "passive"))
    )
    (net (code "77") (name "Net-(D3-PadA)") (class "Default")
      (node (ref "D3") (pin "A") (pinfunction "A_A") (pintype "passive"))
      (node (ref "R5") (pin "1") (pinfunction "1_1") (pintype "passive"))
    )
    (net (code "78") (name "Net-(D4-PadA)") (class "Default")
      (node (ref "D4") (pin "A") (pinfunction "A_A") (pintype "passive"))
      (node (ref "R6") (pin "1") (pinfunction "1_1") (pintype "passive"))
    )
    (net (code "79") (name "Net-(IC1-PB4A)") (class "Default")
      (node (ref "IC1") (pin "27") (pinfunction "PB4A_27") (pintype "bidirectional"))
      (node (ref "IC2") (pin "17") (pinfunction "A3_17") (pintype "passive"))
    )
    (net (code "80") (name "Net-(IC1-PB4B)") (class "Default")
      (node (ref "IC1") (pin "28") (pinfunction "PB4B_28") (pintype "bidirectional"))
      (node (ref "IC2") (pin "18") (pinfunction "A2_18") (pintype "passive"))
    )
    (net (code "81") (name "Net-(IC1-PB4C)") (class "Default")
      (node (ref "IC1") (pin "29") (pinfunction "PB4C_29") (pintype "bidirectional"))
      (node (ref "IC2") (pin "19") (pinfunction "A1_19") (pintype "passive"))
    )
    (net (code "82") (name "Net-(IC1-PB4D)") (class "Default")
      (node (ref "IC1") (pin "30") (pinfunction "PB4D_30") (pintype "bidirectional"))
      (node (ref "IC2") (pin "20") (pinfunction "A0_20") (pintype "passive"))
    )
    (net (code "83") (name "Net-(IC1-PB6A)") (class "Default")
      (node (ref "IC1") (pin "31") (pinfunction "PB6A_31") (pintype "bidirectional"))
      (node (ref "IC2") (pin "21") (pinfunction "I/O0_21") (pintype "bidirectional"))
    )
    (net (code "84") (name "Net-(IC1-PB6B)") (class "Default")
      (node (ref "IC1") (pin "32") (pinfunction "PB6B_32") (pintype "bidirectional"))
      (node (ref "IC2") (pin "22") (pinfunction "I/O1_22") (pintype "bidirectional"))
    )
    (net (code "85") (name "Net-(IC1-PB6C)") (class "Default")
      (node (ref "IC1") (pin "34") (pinfunction "PB6C_34") (pintype "bidirectional"))
      (node (ref "IC2") (pin "23") (pinfunction "I/O2_23") (pintype "bidirectional"))
    )
    (net (code "86") (name "Net-(IC1-PB6D)") (class "Default")
      (node (ref "IC1") (pin "35") (pinfunction "PB6D_35") (pintype "bidirectional"))
      (node (ref "IC2") (pin "25") (pinfunction "I/O3_25") (pintype "bidirectional"))
    )
    (net (code "87") (name "Net-(IC1-PB10A)") (class "Default")
      (node (ref "IC1") (pin "36") (pinfunction "PB10A_36") (pintype "bidirectional"))
      (node (ref "IC2") (pin "26") (pinfunction "I/O4_26") (pintype "bidirectional"))
    )
    (net (code "88") (name "Net-(IC1-PB10B)") (class "Default")
      (node (ref "IC1") (pin "37") (pinfunction "PB10B_37") (pintype "bidirectional"))
      (node (ref "IC2") (pin "27") (pinfunction "I/O5_27") (pintype "bidirectional"))
    )
    (net (code "89") (name "Net-(IC1-PB10C)") (class "Default")
      (node (ref "IC1") (pin "38") (pinfunction "PB10C_38") (pintype "bidirectional"))
      (node (ref "IC2") (pin "28") (pinfunction "I/O6_28") (pintype "bidirectional"))
    )
    (net (code "90") (name "Net-(IC1-PB10D)") (class "Default")
      (node (ref "IC1") (pin "39") (pinfunction "PB10D_39") (pintype "bidirectional"))
      (node (ref "IC2") (pin "29") (pinfunction "I/O7_29") (pintype "bidirectional"))
    )
    (net (code "91") (name "Net-(IC1-PB12A)") (class "Default")
      (node (ref "IC1") (pin "40") (pinfunction "PB12A_40") (pintype "bidirectional"))
      (node (ref "IC2") (pin "31") (pinfunction "A10_31") (pintype "passive"))
    )
    (net (code "92") (name "Net-(IC1-PB12B)") (class "Default")
      (node (ref "IC1") (pin "41") (pinfunction "PB12B_41") (pintype "bidirectional"))
      (node (ref "IC2") (pin "32") (pinfunction "~{OE}_32") (pintype "passive"))
    )
    (net (code "93") (name "Net-(IC1-PL3C)") (class "Default")
      (node (ref "IC1") (pin "9") (pinfunction "PL3C_9") (pintype "bidirectional"))
      (node (ref "PL3C") (pin "1") (pinfunction "1_1") (pintype "bidirectional"))
    )
    (net (code "94") (name "Net-(IC1-PL3D)") (class "Default")
      (node (ref "IC1") (pin "10") (pinfunction "PL3D_10") (pintype "bidirectional"))
      (node (ref "IC2") (pin "16") (pinfunction "A4_16") (pintype "passive"))
    )
    (net (code "95") (name "Net-(IC1-PL5A)") (class "Default")
      (node (ref "IC1") (pin "12") (pinfunction "PL5A_12") (pintype "bidirectional"))
      (node (ref "IC2") (pin "15") (pinfunction "A5_15") (pintype "passive"))
    )
    (net (code "96") (name "Net-(IC1-PL5B)") (class "Default")
      (node (ref "IC1") (pin "13") (pinfunction "PL5B_13") (pintype "bidirectional"))
      (node (ref "IC2") (pin "14") (pinfunction "A6_14") (pintype "passive"))
    )
    (net (code "97") (name "Net-(IC1-PL5C)") (class "Default")
      (node (ref "IC1") (pin "14") (pinfunction "PL5C_14") (pintype "bidirectional"))
      (node (ref "IC2") (pin "13") (pinfunction "A7_13") (pintype "passive"))
    )
    (net (code "98") (name "Net-(IC1-PL5D)") (class "Default")
      (node (ref "IC1") (pin "15") (pinfunction "PL5D_15") (pintype "bidirectional"))
      (node (ref "IC2") (pin "12") (pinfunction "A12_12") (pintype "passive"))
    )
    (net (code "99") (name "Net-(IC1-PL6A)") (class "Default")
      (node (ref "IC1") (pin "16") (pinfunction "PL6A_16") (pintype "bidirectional"))
      (node (ref "IC2") (pin "11") (pinfunction "A14_11") (pintype "passive"))
    )
    (net (code "100") (name "Net-(IC1-PL6B)") (class "Default")
      (node (ref "IC1") (pin "17") (pinfunction "PL6B_17") (pintype "bidirectional"))
      (node (ref "IC2") (pin "10") (pinfunction "A16_10") (pintype "passive"))
    )
    (net (code "101") (name "Net-(IC1-PL6C)") (class "Default")
      (node (ref "IC1") (pin "18") (pinfunction "PL6C_18") (pintype "bidirectional"))
      (node (ref "IC2") (pin "7") (pinfunction "A15_7") (pintype "passive"))
    )
    (net (code "102") (name "Net-(IC1-PL6D)") (class "Default")
      (node (ref "IC1") (pin "19") (pinfunction "PL6D_19") (pintype "bidirectional"))
      (node (ref "IC2") (pin "5") (pinfunction "~{WE}_5") (pintype "passive"))
    )
    (net (code "103") (name "Net-(IC1-PL7A)") (class "Default")
      (node (ref "IC1") (pin "20") (pinfunction "PL7A_20") (pintype "bidirectional"))
      (node (ref "IC2") (pin "4") (pinfunction "A13_4") (pintype "passive"))
    )
    (net (code "104") (name "Net-(IC1-PL7B)") (class "Default")
      (node (ref "IC1") (pin "21") (pinfunction "PL7B_21") (pintype "bidirectional"))
      (node (ref "IC2") (pin "3") (pinfunction "A8_3") (pintype "passive"))
    )
    (net (code "105") (name "Net-(IC1-PL7C)") (class "Default")
      (node (ref "IC1") (pin "24") (pinfunction "PL7C_24") (pintype "bidirectional"))
      (node (ref "IC2") (pin "2") (pinfunction "A9_2") (pintype "passive"))
    )
    (net (code "106") (name "Net-(IC1-PL7D)") (class "Default")
      (node (ref "IC1") (pin "25") (pinfunction "PL7D_25") (pintype "bidirectional"))
      (node (ref "IC2") (pin "1") (pinfunction "A11_1") (pintype "passive"))
    )
    (net (code "107") (name "Net-(IC4-NRST)") (class "Default")
      (node (ref "IC4") (pin "14") (pinfunction "NRST_14") (pintype "bidirectional"))
      (node (ref "NRST") (pin "1") (pinfunction "1_1") (pintype "bidirectional"))
      (node (ref "R3") (pin "2") (pinfunction "2_2") (pintype "passive"))
    )
    (net (code "108") (name "Net-(IC4-PF10)") (class "Default")
      (node (ref "IC4") (pin "11") (pinfunction "PF10_11") (pintype "bidirectional"))
      (node (ref "R6") (pin "2") (pinfunction "2_2") (pintype "passive"))
    )
    (net (code "109") (name "Net-(IC5-1B1)") (class "Default")
      (node (ref "B1") (pin "OUT0") (pinfunction "OUT0_OUT0") (pintype "bidirectional"))
      (node (ref "IC5") (pin "2") (pinfunction "1B1_2") (pintype "bidirectional"))
    )
    (net (code "110") (name "Net-(IC5-1B2)") (class "Default")
      (node (ref "B1") (pin "OUT1") (pinfunction "OUT1_OUT1") (pintype "bidirectional"))
      (node (ref "IC5") (pin "3") (pinfunction "1B2_3") (pintype "bidirectional"))
    )
    (net (code "111") (name "Net-(IC5-1B3)") (class "Default")
      (node (ref "B1") (pin "OUT2") (pinfunction "OUT2_OUT2") (pintype "bidirectional"))
      (node (ref "IC5") (pin "5") (pinfunction "1B3_5") (pintype "bidirectional"))
    )
    (net (code "112") (name "Net-(IC5-1B4)") (class "Default")
      (node (ref "B1") (pin "OUT3") (pinfunction "OUT3_OUT3") (pintype "bidirectional"))
      (node (ref "IC5") (pin "6") (pinfunction "1B4_6") (pintype "bidirectional"))
    )
    (net (code "113") (name "Net-(IC5-1B5)") (class "Default")
      (node (ref "B1") (pin "OUT4") (pinfunction "OUT4_OUT4") (pintype "bidirectional"))
      (node (ref "IC5") (pin "8") (pinfunction "1B5_8") (pintype "bidirectional"))
    )
    (net (code "114") (name "Net-(IC5-1B6)") (class "Default")
      (node (ref "B1") (pin "OUT5") (pinfunction "OUT5_OUT5") (pintype "bidirectional"))
      (node (ref "IC5") (pin "9") (pinfunction "1B6_9") (pintype "bidirectional"))
    )
    (net (code "115") (name "Net-(IC5-1B7)") (class "Default")
      (node (ref "B1") (pin "OUT6") (pinfunction "OUT6_OUT6") (pintype "bidirectional"))
      (node (ref "IC5") (pin "11") (pinfunction "1B7_11") (pintype "bidirectional"))
    )
    (net (code "116") (name "Net-(IC5-1B8)") (class "Default")
      (node (ref "B1") (pin "OUT7") (pinfunction "OUT7_OUT7") (pintype "bidirectional"))
      (node (ref "IC5") (pin "12") (pinfunction "1B8_12") (pintype "bidirectional"))
    )
    (net (code "117") (name "Net-(IC6-BP)") (class "Default")
      (node (ref "C30") (pin "1") (pinfunction "1_1") (pintype "passive"))
      (node (ref "IC6") (pin "4") (pinfunction "BP_4") (pintype "input"))
    )
    (net (code "118") (name "Net-(J1-Pad4)") (class "Default")
      (node (ref "J1") (pin "4") (pinfunction "4_4") (pintype "passive"))
      (node (ref "R1") (pin "1") (pinfunction "1_1") (pintype "passive"))
    )
    (net (code "119") (name "unconnected-(B1-NC-PadNC@1)") (class "Default")
      (node (ref "B1") (pin "NC@1") (pinfunction "NC_NC@1") (pintype "bidirectional"))
    )
    (net (code "120") (name "unconnected-(IC1-NC_1-Pad11)") (class "Default")
      (node (ref "IC1") (pin "11") (pinfunction "NC_1_11") (pintype "no_connect"))
    )
    (net (code "121") (name "unconnected-(IC1-NC_2-Pad61)") (class "Default")
      (node (ref "IC1") (pin "61") (pinfunction "NC_2_61") (pintype "no_connect"))
    )
    (net (code "122") (name "unconnected-(IC1-NC_3-Pad89)") (class "Default")
      (node (ref "IC1") (pin "89") (pinfunction "NC_3_89") (pintype "no_connect"))
    )
    (net (code "123") (name "unconnected-(IC2-NC-Pad9)") (class "Default")
      (node (ref "IC2") (pin "9") (pinfunction "NC_9") (pintype "no_connect"))
    )
    (net (code "124") (name "unconnected-(IC3-NC-Pad9)") (class "Default")
      (node (ref "IC3") (pin "9") (pinfunction "NC_9") (pintype "no_connect"))
    )
    (net (code "125") (name "unconnected-(IC4-PA9-Pad68)") (class "Default")
      (node (ref "IC4") (pin "68") (pinfunction "PA9_68") (pintype "bidirectional"))
    )
    (net (code "126") (name "unconnected-(IC4-PA10-Pad69)") (class "Default")
      (node (ref "IC4") (pin "69") (pinfunction "PA10_69") (pintype "bidirectional"))
    )
    (net (code "127") (name "unconnected-(IC4-PA13-Pad72)") (class "Default")
      (node (ref "IC4") (pin "72") (pinfunction "PA13_72") (pintype "bidirectional"))
    )
    (net (code "128") (name "unconnected-(IC4-PA14-Pad76)") (class "Default")
      (node (ref "IC4") (pin "76") (pinfunction "PA14_76") (pintype "bidirectional"))
    )
    (net (code "129") (name "unconnected-(IC4-PA15-Pad77)") (class "Default")
      (node (ref "IC4") (pin "77") (pinfunction "PA15_77") (pintype "bidirectional"))
    )
    (net (code "130") (name "unconnected-(IC4-PC13-Pad7)") (class "Default")
      (node (ref "IC4") (pin "7") (pinfunction "PC13_7") (pintype "bidirectional"))
    )
    (net (code "131") (name "unconnected-(IC4-PC14-OSC32_IN-Pad8)") (class "Default")
      (node (ref "IC4") (pin "8") (pinfunction "PC14-OSC32_IN_8") (pintype "bidirectional"))
    )
    (net (code "132") (name "unconnected-(IC4-PC15-OSC32_OUT-Pad9)") (class "Default")
      (node (ref "IC4") (pin "9") (pinfunction "PC15-OSC32_OUT_9") (pintype "bidirectional"))
    )
    (net (code "133") (name "unconnected-(IC4-PD8-Pad55)") (class "Default")
      (node (ref "IC4") (pin "55") (pinfunction "PD8_55") (pintype "bidirectional"))
    )
    (net (code "134") (name "unconnected-(IC4-PD9-Pad56)") (class "Default")
      (node (ref "IC4") (pin "56") (pinfunction "PD9_56") (pintype "bidirectional"))
    )
    (net (code "135") (name "unconnected-(IC4-PD10-Pad57)") (class "Default")
      (node (ref "IC4") (pin "57") (pinfunction "PD10_57") (pintype "bidirectional"))
    )
    (net (code "136") (name "unconnected-(IC4-PD11-Pad58)") (class "Default")
      (node (ref "IC4") (pin "58") (pinfunction "PD11_58") (pintype "bidirectional"))
    )
    (net (code "137") (name "unconnected-(IC4-PD12-Pad59)") (class "Default")
      (node (ref "IC4") (pin "59") (pinfunction "PD12_59") (pintype "bidirectional"))
    )
    (net (code "138") (name "unconnected-(IC4-PD13-Pad60)") (class "Default")
      (node (ref "IC4") (pin "60") (pinfunction "PD13_60") (pintype "bidirectional"))
    )
    (net (code "139") (name "unconnected-(IC4-PD14-Pad61)") (class "Default")
      (node (ref "IC4") (pin "61") (pinfunction "PD14_61") (pintype "bidirectional"))
    )
    (net (code "140") (name "unconnected-(IC4-PD15-Pad62)") (class "Default")
      (node (ref "IC4") (pin "62") (pinfunction "PD15_62") (pintype "bidirectional"))
    )
    (net (code "141") (name "unconnected-(IC4-PF0-OSC_IN-Pad12)") (class "Default")
      (node (ref "IC4") (pin "12") (pinfunction "PF0-OSC_IN_12") (pintype "bidirectional"))
    )
    (net (code "142") (name "unconnected-(IC4-PF1-OSC_OUT-Pad13)") (class "Default")
      (node (ref "IC4") (pin "13") (pinfunction "PF1-OSC_OUT_13") (pintype "bidirectional"))
    )
    (net (code "143") (name "unconnected-(IC4-PF2-Pad19)") (class "Default")
      (node (ref "IC4") (pin "19") (pinfunction "PF2_19") (pintype "bidirectional"))
    )
    (net (code "144") (name "unconnected-(IC4-PF3-Pad22)") (class "Default")
      (node (ref "IC4") (pin "22") (pinfunction "PF3_22") (pintype "bidirectional"))
    )
    (net (code "145") (name "unconnected-(IC4-PF6-Pad73)") (class "Default")
      (node (ref "IC4") (pin "73") (pinfunction "PF6_73") (pintype "bidirectional"))
    )
    (net (code "146") (name "unconnected-(IC4-PF9-Pad10)") (class "Default")
      (node (ref "IC4") (pin "10") (pinfunction "PF9_10") (pintype "bidirectional"))
    )
    (net (code "147") (name "unconnected-(IC4-VBAT-Pad6)") (class "Default")
      (node (ref "IC4") (pin "6") (pinfunction "VBAT_6") (pintype "bidirectional"))
    )
    (net (code "148") (name "unconnected-(IC5-2A3-Pad33)") (class "Default")
      (node (ref "IC5") (pin "33") (pinfunction "2A3_33") (pintype "bidirectional"))
    )
    (net (code "149") (name "unconnected-(IC5-2A4-Pad32)") (class "Default")
      (node (ref "IC5") (pin "32") (pinfunction "2A4_32") (pintype "bidirectional"))
    )
    (net (code "150") (name "unconnected-(IC5-2A5-Pad30)") (class "Default")
      (node (ref "IC5") (pin "30") (pinfunction "2A5_30") (pintype "bidirectional"))
    )
    (net (code "151") (name "unconnected-(IC5-2A6-Pad29)") (class "Default")
      (node (ref "IC5") (pin "29") (pinfunction "2A6_29") (pintype "bidirectional"))
    )
    (net (code "152") (name "unconnected-(IC5-2A7-Pad27)") (class "Default")
      (node (ref "IC5") (pin "27") (pinfunction "2A7_27") (pintype "bidirectional"))
    )
    (net (code "153") (name "unconnected-(IC5-2A8-Pad26)") (class "Default")
      (node (ref "IC5") (pin "26") (pinfunction "2A8_26") (pintype "bidirectional"))
    )
    (net (code "154") (name "unconnected-(IC5-2B3-Pad16)") (class "Default")
      (node (ref "IC5") (pin "16") (pinfunction "2B3_16") (pintype "bidirectional"))
    )
    (net (code "155") (name "unconnected-(IC5-2B4-Pad17)") (class "Default")
      (node (ref "IC5") (pin "17") (pinfunction "2B4_17") (pintype "bidirectional"))
    )
    (net (code "156") (name "unconnected-(IC5-2B5-Pad19)") (class "Default")
      (node (ref "IC5") (pin "19") (pinfunction "2B5_19") (pintype "bidirectional"))
    )
    (net (code "157") (name "unconnected-(IC5-2B6-Pad20)") (class "Default")
      (node (ref "IC5") (pin "20") (pinfunction "2B6_20") (pintype "bidirectional"))
    )
    (net (code "158") (name "unconnected-(IC5-2B7-Pad22)") (class "Default")
      (node (ref "IC5") (pin "22") (pinfunction "2B7_22") (pintype "bidirectional"))
    )
    (net (code "159") (name "unconnected-(IC5-2B8-Pad23)") (class "Default")
      (node (ref "IC5") (pin "23") (pinfunction "2B8_23") (pintype "bidirectional"))
    )
    (net (code "160") (name "unconnected-(J2-Pad3)") (class "Default")
      (node (ref "J2") (pin "3") (pinfunction "3_3") (pintype "passive"))
    )
  )
)
